# ecg.net
KiCad netlist of a schematic drawn in EAGLE
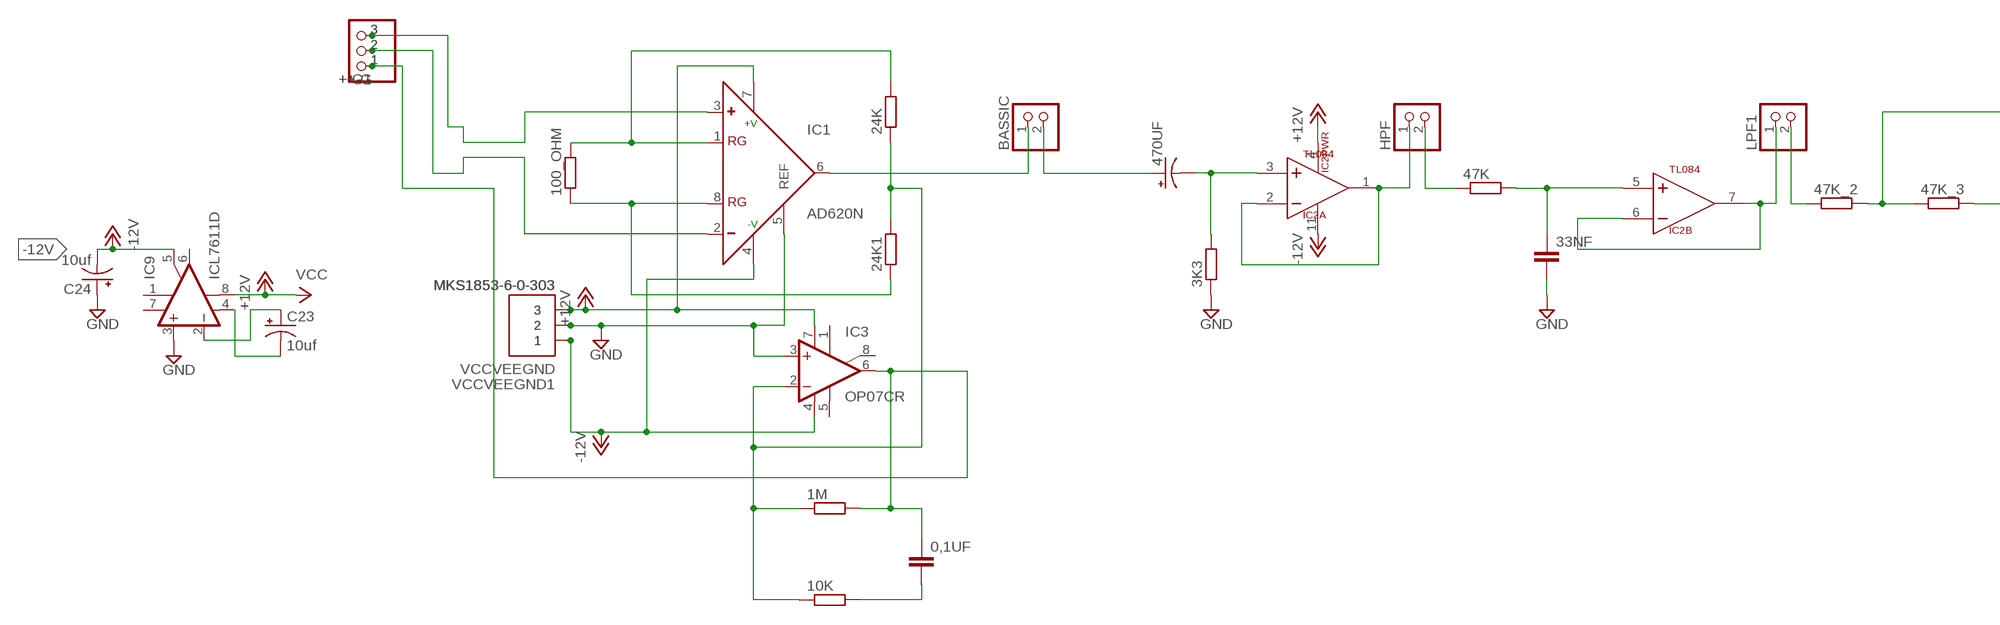
[diagram p0: schematic, sheet 1, part 1 of 2]
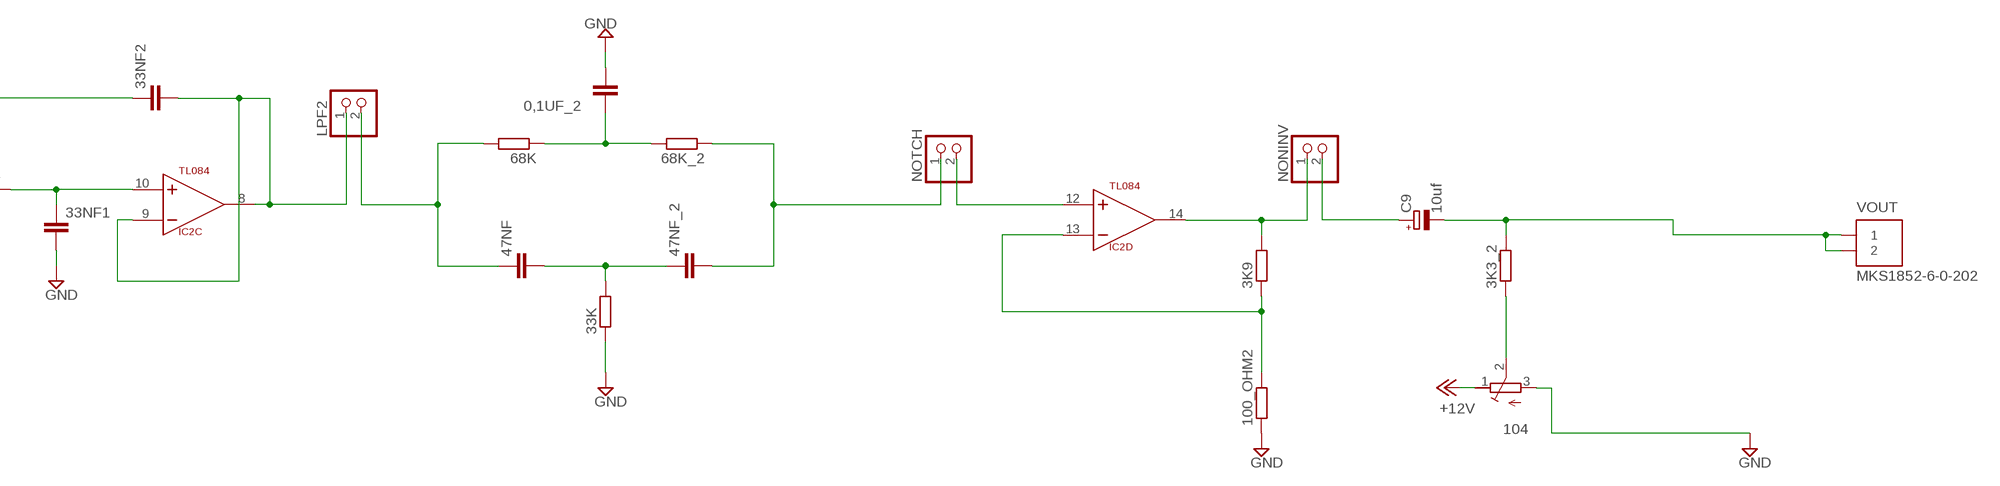
[diagram p1: schematic, sheet 1, part 2 of 2]

(export (version "E")
  (design (tool "Eeschema 10.0.6"))
  (components
    (comp (ref "+-G")
      (value "PINHD-1X3")
      (footprint "eagle-import:1X03")
      (libsource (lib "eagle-import") (part "PINHD-1X3"))
    )
    (comp (ref "+-G1")
      (value "PINHD-1X3")
      (footprint "eagle-import:1X03")
      (libsource (lib "eagle-import") (part "PINHD-1X3"))
    )
    (comp (ref "0,1UF")
      (value "C-EUC1206")
      (footprint "eagle-import:C1206")
      (libsource (lib "eagle-import") (part "C-EUC1206"))
    )
    (comp (ref "0,1UF_2")
      (value "C-EUC1206")
      (footprint "eagle-import:C1206")
      (libsource (lib "eagle-import") (part "C-EUC1206"))
    )
    (comp (ref "1M")
      (value "R-EU_R1206")
      (footprint "eagle-import:R1206")
      (libsource (lib "eagle-import") (part "R-EU_R1206"))
    )
    (comp (ref "3K3")
      (value "R-EU_M1206")
      (footprint "eagle-import:M1206")
      (libsource (lib "eagle-import") (part "R-EU_M1206"))
    )
    (comp (ref "3K3_2")
      (value "R-EU_R1206")
      (footprint "eagle-import:R1206")
      (libsource (lib "eagle-import") (part "R-EU_R1206"))
    )
    (comp (ref "3K9")
      (value "R-EU_R1206")
      (footprint "eagle-import:R1206")
      (libsource (lib "eagle-import") (part "R-EU_R1206"))
    )
    (comp (ref "10K")
      (value "R-EU_M1206")
      (footprint "eagle-import:M1206")
      (libsource (lib "eagle-import") (part "R-EU_M1206"))
    )
    (comp (ref "24K")
      (value "R-EU_M1206")
      (footprint "eagle-import:M1206")
      (libsource (lib "eagle-import") (part "R-EU_M1206"))
    )
    (comp (ref "24K1")
      (value "R-EU_M1206")
      (footprint "eagle-import:M1206")
      (libsource (lib "eagle-import") (part "R-EU_M1206"))
    )
    (comp (ref "33K")
      (value "R-EU_R1206")
      (footprint "eagle-import:R1206")
      (libsource (lib "eagle-import") (part "R-EU_R1206"))
    )
    (comp (ref "33NF")
      (value "C-EUC1206")
      (footprint "eagle-import:C1206")
      (libsource (lib "eagle-import") (part "C-EUC1206"))
    )
    (comp (ref "33NF1")
      (value "C-EUC1206")
      (footprint "eagle-import:C1206")
      (libsource (lib "eagle-import") (part "C-EUC1206"))
    )
    (comp (ref "33NF2")
      (value "C-EUC1206")
      (footprint "eagle-import:C1206")
      (libsource (lib "eagle-import") (part "C-EUC1206"))
    )
    (comp (ref "47K")
      (value "R-EU_M1206")
      (footprint "eagle-import:M1206")
      (libsource (lib "eagle-import") (part "R-EU_M1206"))
    )
    (comp (ref "47K_2")
      (value "R-EU_R1206")
      (footprint "eagle-import:R1206")
      (libsource (lib "eagle-import") (part "R-EU_R1206"))
    )
    (comp (ref "47K_3")
      (value "R-EU_R1206")
      (footprint "eagle-import:R1206")
      (libsource (lib "eagle-import") (part "R-EU_R1206"))
    )
    (comp (ref "47NF")
      (value "C-EUC1206")
      (footprint "eagle-import:C1206")
      (libsource (lib "eagle-import") (part "C-EUC1206"))
    )
    (comp (ref "47NF_2")
      (value "C-EUC1206")
      (footprint "eagle-import:C1206")
      (libsource (lib "eagle-import") (part "C-EUC1206"))
    )
    (comp (ref "68K")
      (value "R-EU_R1206")
      (footprint "eagle-import:R1206")
      (libsource (lib "eagle-import") (part "R-EU_R1206"))
    )
    (comp (ref "68K_2")
      (value "R-EU_R1206")
      (footprint "eagle-import:R1206")
      (libsource (lib "eagle-import") (part "R-EU_R1206"))
    )
    (comp (ref "100_OHM")
      (value "R-EU_M1206")
      (footprint "eagle-import:M1206")
      (libsource (lib "eagle-import") (part "R-EU_M1206"))
    )
    (comp (ref "100_OHM2")
      (value "R-EU_R1206")
      (footprint "eagle-import:R1206")
      (libsource (lib "eagle-import") (part "R-EU_R1206"))
    )
    (comp (ref "104")
      (value "R-TRIMMT93YA")
      (footprint "eagle-import:RTRIMT93YA")
      (libsource (lib "eagle-import") (part "R-TRIMMT93YA"))
    )
    (comp (ref "470UF")
      (value "CPOL-US140CLH-1010")
      (footprint "eagle-import:140CLH-1010")
      (libsource (lib "eagle-import") (part "CPOL-US140CLH-1010"))
    )
    (comp (ref "BASSIC")
      (value "PINHD-1X2")
      (footprint "eagle-import:1X02")
      (libsource (lib "eagle-import") (part "PINHD-1X2"))
    )
    (comp (ref "C9")
      (value "10uf")
      (footprint "eagle-import:140CLH-0810")
      (libsource (lib "eagle-import") (part "CPOL-EU140CLH-0810"))
    )
    (comp (ref "C23")
      (value "10uf")
      (footprint "eagle-import:150CLZ-0810")
      (libsource (lib "eagle-import") (part "CPOL-US150CLZ-0810"))
    )
    (comp (ref "C24")
      (value "10uf")
      (footprint "eagle-import:150CLZ-0810")
      (libsource (lib "eagle-import") (part "CPOL-US150CLZ-0810"))
    )
    (comp (ref "HPF")
      (value "PINHD-1X2")
      (footprint "eagle-import:1X02")
      (libsource (lib "eagle-import") (part "PINHD-1X2"))
    )
    (comp (ref "IC1")
      (value "AD620N")
      (footprint "eagle-import:DIL08")
      (fields (field (name "MF") "ALTERA CORPORATION") (field (name "MPN") "AD620AN"))
      (libsource (lib "eagle-import") (part "AD620N"))
    )
    (comp (ref "IC2")
      (value "TL084")
      (footprint "eagle-import:SO14")
      (libsource (lib "eagle-import") (part "TL084"))
    )
    (comp (ref "IC3")
      (value "OP07CR")
      (footprint "eagle-import:SO08")
      (libsource (lib "eagle-import") (part "OP07RC"))
    )
    (comp (ref "IC9")
      (value "ICL7611D")
      (footprint "eagle-import:SO08")
      (libsource (lib "eagle-import") (part "ICL7611D"))
    )
    (comp (ref "LPF1")
      (value "PINHD-1X2")
      (footprint "eagle-import:1X02")
      (libsource (lib "eagle-import") (part "PINHD-1X2"))
    )
    (comp (ref "LPF2")
      (value "PINHD-1X2")
      (footprint "eagle-import:1X02")
      (libsource (lib "eagle-import") (part "PINHD-1X2"))
    )
    (comp (ref "NONINV")
      (value "PINHD-1X2")
      (footprint "eagle-import:1X02")
      (libsource (lib "eagle-import") (part "PINHD-1X2"))
    )
    (comp (ref "NOTCH")
      (value "PINHD-1X2")
      (footprint "eagle-import:1X02")
      (libsource (lib "eagle-import") (part "PINHD-1X2"))
    )
    (comp (ref "VCCVEEGND")
      (value "MKS1853-6-0-303")
      (footprint "eagle-import:MKS1853-6-0-303")
      (libsource (lib "eagle-import") (part "MKS1853-6-0-303"))
    )
    (comp (ref "VCCVEEGND1")
      (value "MKS1853-6-0-303")
      (footprint "eagle-import:MKS1853-6-0-303")
      (libsource (lib "eagle-import") (part "MKS1853-6-0-303"))
    )
    (comp (ref "VOUT")
      (value "MKS1852-6-0-202")
      (footprint "eagle-import:MKS1852-6-0-202")
      (libsource (lib "eagle-import") (part "MKS1852-6-0-202"))
    )
  )
  (nets
    (net (code "1") (name "+12V") (class "Default")
      (node (ref "104") (pin "1") (pinfunction "E_1") (pintype "passive"))
      (node (ref "IC1") (pin "7") (pinfunction "+V_7") (pintype "power_in"))
      (node (ref "IC2") (pin "4") (pinfunction "VCC+_4") (pintype "power_in"))
      (node (ref "IC3") (pin "7") (pinfunction "V+_7") (pintype "power_in"))
      (node (ref "IC9") (pin "8") (pinfunction "OPT_8") (pintype "passive"))
      (node (ref "VCCVEEGND") (pin "3") (pinfunction "3_3") (pintype "input"))
      (node (ref "VCCVEEGND1") (pin "3") (pinfunction "3_3") (pintype "input"))
    )
    (net (code "2") (name "-12V") (class "Default")
      (node (ref "C24") (pin "-") (pinfunction "-_-") (pintype "passive"))
      (node (ref "IC1") (pin "4") (pinfunction "-V_4") (pintype "power_in"))
      (node (ref "IC2") (pin "11") (pinfunction "VCC-_11") (pintype "power_in"))
      (node (ref "IC3") (pin "4") (pinfunction "V-_4") (pintype "power_in"))
      (node (ref "IC9") (pin "5") (pinfunction "ON2_5") (pintype "passive"))
      (node (ref "VCCVEEGND") (pin "1") (pinfunction "1_1") (pintype "input"))
      (node (ref "VCCVEEGND1") (pin "1") (pinfunction "1_1") (pintype "input"))
    )
    (net (code "3") (name "/V+") (class "Default")
      (node (ref "IC9") (pin "7") (pinfunction "V+_7") (pintype "power_in"))
    )
    (net (code "4") (name "GND") (class "Default")
      (node (ref "0,1UF_2") (pin "2") (pinfunction "2_2") (pintype "passive"))
      (node (ref "100_OHM2") (pin "1") (pinfunction "1_1") (pintype "passive"))
      (node (ref "104") (pin "3") (pinfunction "A_3") (pintype "passive"))
      (node (ref "33K") (pin "1") (pinfunction "1_1") (pintype "passive"))
      (node (ref "33NF") (pin "2") (pinfunction "2_2") (pintype "passive"))
      (node (ref "33NF1") (pin "2") (pinfunction "2_2") (pintype "passive"))
      (node (ref "3K3") (pin "1") (pinfunction "1_1") (pintype "passive"))
      (node (ref "C24") (pin "+") (pinfunction "+_+") (pintype "passive"))
      (node (ref "IC1") (pin "5") (pinfunction "REF_5") (pintype "passive"))
      (node (ref "IC3") (pin "3") (pinfunction "+IN_3") (pintype "input"))
      (node (ref "IC9") (pin "3") (pinfunction "+IN_3") (pintype "input"))
      (node (ref "VCCVEEGND") (pin "2") (pinfunction "2_2") (pintype "input"))
      (node (ref "VCCVEEGND1") (pin "2") (pinfunction "2_2") (pintype "input"))
    )
    (net (code "5") (name "Net-(0,1UF-Pad2)") (class "Default")
      (node (ref "0,1UF") (pin "2") (pinfunction "2_2") (pintype "passive"))
      (node (ref "10K") (pin "2") (pinfunction "2_2") (pintype "passive"))
    )
    (net (code "6") (name "Net-(0,1UF_2-Pad1)") (class "Default")
      (node (ref "0,1UF_2") (pin "1") (pinfunction "1_1") (pintype "passive"))
      (node (ref "68K") (pin "1") (pinfunction "1_1") (pintype "passive"))
      (node (ref "68K_2") (pin "2") (pinfunction "2_2") (pintype "passive"))
    )
    (net (code "7") (name "Net-(3K3_2-Pad2)") (class "Default")
      (node (ref "3K3_2") (pin "2") (pinfunction "2_2") (pintype "passive"))
      (node (ref "C9") (pin "-") (pinfunction "-_-") (pintype "passive"))
      (node (ref "VOUT") (pin "1") (pinfunction "1_1") (pintype "input"))
      (node (ref "VOUT") (pin "2") (pinfunction "2_2") (pintype "input"))
    )
    (net (code "8") (name "Net-(33K-Pad2)") (class "Default")
      (node (ref "33K") (pin "2") (pinfunction "2_2") (pintype "passive"))
      (node (ref "47NF") (pin "2") (pinfunction "2_2") (pintype "passive"))
      (node (ref "47NF_2") (pin "1") (pinfunction "1_1") (pintype "passive"))
    )
    (net (code "9") (name "Net-(33NF2-Pad1)") (class "Default")
      (node (ref "33NF2") (pin "1") (pinfunction "1_1") (pintype "passive"))
      (node (ref "47K_2") (pin "2") (pinfunction "2_2") (pintype "passive"))
      (node (ref "47K_3") (pin "1") (pinfunction "1_1") (pintype "passive"))
    )
    (net (code "10") (name "Net-(47K-Pad1)") (class "Default")
      (node (ref "47K") (pin "1") (pinfunction "1_1") (pintype "passive"))
      (node (ref "HPF") (pin "2") (pinfunction "2_2") (pintype "passive"))
    )
    (net (code "11") (name "Net-(47K_2-Pad1)") (class "Default")
      (node (ref "47K_2") (pin "1") (pinfunction "1_1") (pintype "passive"))
      (node (ref "LPF1") (pin "2") (pinfunction "2_2") (pintype "passive"))
    )
    (net (code "12") (name "Net-(47NF-Pad1)") (class "Default")
      (node (ref "47NF") (pin "1") (pinfunction "1_1") (pintype "passive"))
      (node (ref "68K") (pin "2") (pinfunction "2_2") (pintype "passive"))
      (node (ref "LPF2") (pin "2") (pinfunction "2_2") (pintype "passive"))
    )
    (net (code "13") (name "Net-(47NF_2-Pad2)") (class "Default")
      (node (ref "47NF_2") (pin "2") (pinfunction "2_2") (pintype "passive"))
      (node (ref "68K_2") (pin "1") (pinfunction "1_1") (pintype "passive"))
      (node (ref "NOTCH") (pin "1") (pinfunction "1_1") (pintype "passive"))
    )
    (net (code "14") (name "Net-(100_OHM-Pad1)") (class "Default")
      (node (ref "100_OHM") (pin "1") (pinfunction "1_1") (pintype "passive"))
      (node (ref "24K1") (pin "1") (pinfunction "1_1") (pintype "passive"))
      (node (ref "IC1") (pin "8") (pinfunction "RG_8") (pintype "passive"))
    )
    (net (code "15") (name "Net-(100_OHM-Pad2)") (class "Default")
      (node (ref "100_OHM") (pin "2") (pinfunction "2_2") (pintype "passive"))
      (node (ref "24K") (pin "2") (pinfunction "2_2") (pintype "passive"))
      (node (ref "IC1") (pin "1") (pinfunction "RG_1") (pintype "passive"))
    )
    (net (code "16") (name "Net-(104-S)") (class "Default")
      (node (ref "104") (pin "2") (pinfunction "S_2") (pintype "passive"))
      (node (ref "3K3_2") (pin "1") (pinfunction "1_1") (pintype "passive"))
    )
    (net (code "17") (name "Net-(470UF-Pad+)") (class "Default")
      (node (ref "470UF") (pin "+") (pinfunction "+_+") (pintype "passive"))
      (node (ref "BASSIC") (pin "2") (pinfunction "2_2") (pintype "passive"))
    )
    (net (code "18") (name "Net-(C9-Pad+)") (class "Default")
      (node (ref "C9") (pin "+") (pinfunction "+_+") (pintype "passive"))
      (node (ref "NONINV") (pin "2") (pinfunction "2_2") (pintype "passive"))
    )
    (net (code "19") (name "Net-(IC1-+)") (class "Default")
      (node (ref "+-G") (pin "3") (pinfunction "3_3") (pintype "passive"))
      (node (ref "+-G1") (pin "3") (pinfunction "3_3") (pintype "passive"))
      (node (ref "IC1") (pin "3") (pinfunction "+_3") (pintype "input"))
    )
    (net (code "20") (name "Net-(IC1--)") (class "Default")
      (node (ref "+-G") (pin "2") (pinfunction "2_2") (pintype "passive"))
      (node (ref "+-G1") (pin "2") (pinfunction "2_2") (pintype "passive"))
      (node (ref "IC1") (pin "2") (pinfunction "-_2") (pintype "input"))
    )
    (net (code "21") (name "Net-(IC1-OUT)") (class "Default")
      (node (ref "BASSIC") (pin "1") (pinfunction "1_1") (pintype "passive"))
      (node (ref "IC1") (pin "6") (pinfunction "OUT_6") (pintype "output"))
    )
    (net (code "22") (name "Net-(IC2A-IN+)") (class "Default")
      (node (ref "3K3") (pin "2") (pinfunction "2_2") (pintype "passive"))
      (node (ref "470UF") (pin "-") (pinfunction "-_-") (pintype "passive"))
      (node (ref "IC2") (pin "3") (pinfunction "IN+_3") (pintype "input"))
    )
    (net (code "23") (name "Net-(IC2A-IN-)") (class "Default")
      (node (ref "HPF") (pin "1") (pinfunction "1_1") (pintype "passive"))
      (node (ref "IC2") (pin "1") (pinfunction "OUT_1") (pintype "output"))
      (node (ref "IC2") (pin "2") (pinfunction "IN-_2") (pintype "input"))
    )
    (net (code "24") (name "Net-(IC2B-IN+)") (class "Default")
      (node (ref "33NF") (pin "1") (pinfunction "1_1") (pintype "passive"))
      (node (ref "47K") (pin "2") (pinfunction "2_2") (pintype "passive"))
      (node (ref "IC2") (pin "5") (pinfunction "IN+_5") (pintype "input"))
    )
    (net (code "25") (name "Net-(IC2B-IN-)") (class "Default")
      (node (ref "IC2") (pin "6") (pinfunction "IN-_6") (pintype "input"))
      (node (ref "IC2") (pin "7") (pinfunction "OUT_7") (pintype "output"))
      (node (ref "LPF1") (pin "1") (pinfunction "1_1") (pintype "passive"))
    )
    (net (code "26") (name "Net-(IC2C-IN+)") (class "Default")
      (node (ref "33NF1") (pin "1") (pinfunction "1_1") (pintype "passive"))
      (node (ref "47K_3") (pin "2") (pinfunction "2_2") (pintype "passive"))
      (node (ref "IC2") (pin "10") (pinfunction "IN+_10") (pintype "input"))
    )
    (net (code "27") (name "Net-(IC2C-IN-)") (class "Default")
      (node (ref "33NF2") (pin "2") (pinfunction "2_2") (pintype "passive"))
      (node (ref "IC2") (pin "8") (pinfunction "OUT_8") (pintype "output"))
      (node (ref "IC2") (pin "9") (pinfunction "IN-_9") (pintype "input"))
      (node (ref "LPF2") (pin "1") (pinfunction "1_1") (pintype "passive"))
    )
    (net (code "28") (name "Net-(IC2D-IN+)") (class "Default")
      (node (ref "IC2") (pin "12") (pinfunction "IN+_12") (pintype "input"))
      (node (ref "NOTCH") (pin "2") (pinfunction "2_2") (pintype "passive"))
    )
    (net (code "29") (name "Net-(IC2D-IN-)") (class "Default")
      (node (ref "100_OHM2") (pin "2") (pinfunction "2_2") (pintype "passive"))
      (node (ref "3K9") (pin "1") (pinfunction "1_1") (pintype "passive"))
      (node (ref "IC2") (pin "13") (pinfunction "IN-_13") (pintype "input"))
    )
    (net (code "30") (name "Net-(IC2D-OUT)") (class "Default")
      (node (ref "3K9") (pin "2") (pinfunction "2_2") (pintype "passive"))
      (node (ref "IC2") (pin "14") (pinfunction "OUT_14") (pintype "output"))
      (node (ref "NONINV") (pin "1") (pinfunction "1_1") (pintype "passive"))
    )
    (net (code "31") (name "Net-(IC3--IN)") (class "Default")
      (node (ref "10K") (pin "1") (pinfunction "1_1") (pintype "passive"))
      (node (ref "1M") (pin "1") (pinfunction "1_1") (pintype "passive"))
      (node (ref "24K") (pin "1") (pinfunction "1_1") (pintype "passive"))
      (node (ref "24K1") (pin "2") (pinfunction "2_2") (pintype "passive"))
      (node (ref "IC3") (pin "2") (pinfunction "-IN_2") (pintype "input"))
    )
    (net (code "32") (name "Net-(IC3-OUT)") (class "Default")
      (node (ref "+-G") (pin "1") (pinfunction "1_1") (pintype "passive"))
      (node (ref "+-G1") (pin "1") (pinfunction "1_1") (pintype "passive"))
      (node (ref "0,1UF") (pin "1") (pinfunction "1_1") (pintype "passive"))
      (node (ref "1M") (pin "2") (pinfunction "2_2") (pintype "passive"))
      (node (ref "IC3") (pin "6") (pinfunction "OUT_6") (pintype "output"))
    )
    (net (code "33") (name "Net-(IC9--IN)") (class "Default")
      (node (ref "C23") (pin "+") (pinfunction "+_+") (pintype "passive"))
      (node (ref "IC9") (pin "2") (pinfunction "-IN_2") (pintype "input"))
    )
    (net (code "34") (name "Net-(IC9-V-)") (class "Default")
      (node (ref "C23") (pin "-") (pinfunction "-_-") (pintype "passive"))
      (node (ref "IC9") (pin "4") (pinfunction "V-_4") (pintype "power_in"))
    )
    (net (code "35") (name "unconnected-(IC3-ON1-Pad1)") (class "Default")
      (node (ref "IC3") (pin "1") (pinfunction "ON1_1") (pintype "passive"))
    )
    (net (code "36") (name "unconnected-(IC3-ON2-Pad8)") (class "Default")
      (node (ref "IC3") (pin "8") (pinfunction "ON2_8") (pintype "passive"))
    )
    (net (code "37") (name "unconnected-(IC3-OPT-Pad5)") (class "Default")
      (node (ref "IC3") (pin "5") (pinfunction "OPT_5") (pintype "passive"))
    )
    (net (code "38") (name "unconnected-(IC9-ON1-Pad1)") (class "Default")
      (node (ref "IC9") (pin "1") (pinfunction "ON1_1") (pintype "passive"))
    )
    (net (code "39") (name "unconnected-(IC9-OUT-Pad6)") (class "Default")
      (node (ref "IC9") (pin "6") (pinfunction "OUT_6") (pintype "output"))
    )
  )
)
